# rgb_sensor.net
KiCad netlist of a schematic drawn in EAGLE
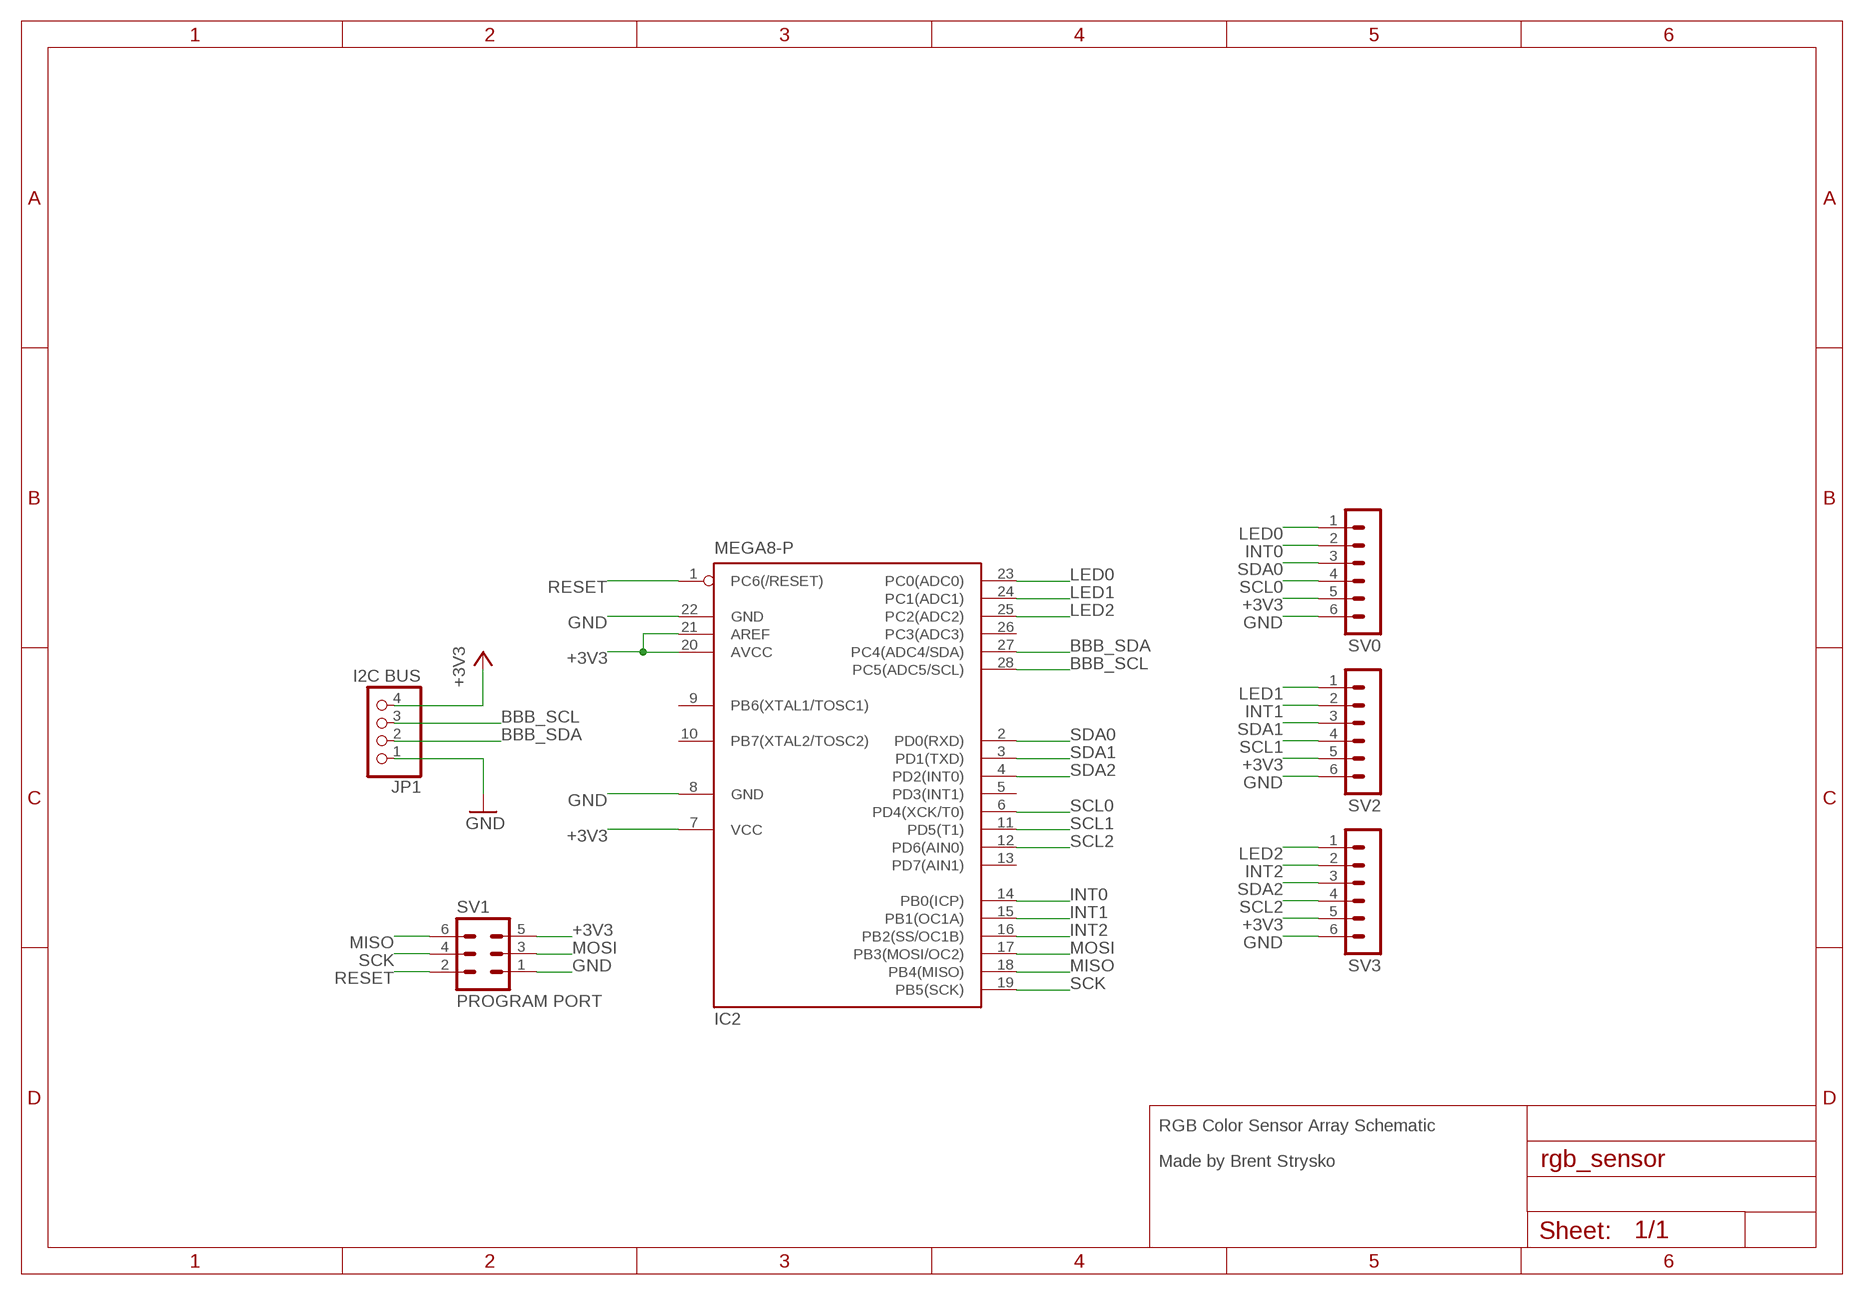
[diagram p0: schematic, sheet 1]

(export (version "E")
  (design (tool "Eeschema 10.0.6"))
  (components
    (comp (ref "IC2")
      (value "MEGA8-P")
      (footprint "eagle-import:DIL28-3")
      (libsource (lib "eagle-import") (part "MEGA8-P"))
    )
    (comp (ref "JP1")
      (value "I2C BUS")
      (footprint "eagle-import:1X04")
      (libsource (lib "eagle-import") (part "PINHD-1X4"))
    )
    (comp (ref "SV0")
      (value "MA06-1")
      (footprint "eagle-import:MA06-1")
      (libsource (lib "eagle-import") (part "MA06-1"))
    )
    (comp (ref "SV1")
      (value "PROGRAM PORT")
      (footprint "eagle-import:MA03-2")
      (libsource (lib "eagle-import") (part "MA03-2"))
    )
    (comp (ref "SV2")
      (value "MA06-1")
      (footprint "eagle-import:MA06-1")
      (libsource (lib "eagle-import") (part "MA06-1"))
    )
    (comp (ref "SV3")
      (value "MA06-1")
      (footprint "eagle-import:MA06-1")
      (libsource (lib "eagle-import") (part "MA06-1"))
    )
  )
  (nets
    (net (code "1") (name "+3V3") (class "Default")
      (node (ref "IC2") (pin "20") (pinfunction "AVCC_20") (pintype "power_in"))
      (node (ref "IC2") (pin "21") (pinfunction "AREF_21") (pintype "passive"))
      (node (ref "IC2") (pin "7") (pinfunction "VCC_7") (pintype "power_in"))
      (node (ref "JP1") (pin "4") (pinfunction "4_4") (pintype "passive"))
      (node (ref "SV0") (pin "5") (pinfunction "5_5") (pintype "passive"))
      (node (ref "SV1") (pin "5") (pinfunction "5_5") (pintype "passive"))
      (node (ref "SV2") (pin "5") (pinfunction "5_5") (pintype "passive"))
      (node (ref "SV3") (pin "5") (pinfunction "5_5") (pintype "passive"))
    )
    (net (code "2") (name "/BBB_SCL") (class "Default")
      (node (ref "IC2") (pin "28") (pinfunction "PC5(ADC5/SCL)_28") (pintype "bidirectional"))
      (node (ref "JP1") (pin "3") (pinfunction "3_3") (pintype "passive"))
    )
    (net (code "3") (name "/BBB_SDA") (class "Default")
      (node (ref "IC2") (pin "27") (pinfunction "PC4(ADC4/SDA)_27") (pintype "bidirectional"))
      (node (ref "JP1") (pin "2") (pinfunction "2_2") (pintype "passive"))
    )
    (net (code "4") (name "/INT0") (class "Default")
      (node (ref "IC2") (pin "14") (pinfunction "PB0(ICP)_14") (pintype "bidirectional"))
      (node (ref "SV0") (pin "2") (pinfunction "2_2") (pintype "passive"))
    )
    (net (code "5") (name "/INT1") (class "Default")
      (node (ref "IC2") (pin "15") (pinfunction "PB1(OC1A)_15") (pintype "bidirectional"))
      (node (ref "SV2") (pin "2") (pinfunction "2_2") (pintype "passive"))
    )
    (net (code "6") (name "/INT2") (class "Default")
      (node (ref "IC2") (pin "16") (pinfunction "PB2(SS/OC1B)_16") (pintype "bidirectional"))
      (node (ref "SV3") (pin "2") (pinfunction "2_2") (pintype "passive"))
    )
    (net (code "7") (name "/LED0") (class "Default")
      (node (ref "IC2") (pin "23") (pinfunction "PC0(ADC0)_23") (pintype "bidirectional"))
      (node (ref "SV0") (pin "1") (pinfunction "1_1") (pintype "passive"))
    )
    (net (code "8") (name "/LED1") (class "Default")
      (node (ref "IC2") (pin "24") (pinfunction "PC1(ADC1)_24") (pintype "bidirectional"))
      (node (ref "SV2") (pin "1") (pinfunction "1_1") (pintype "passive"))
    )
    (net (code "9") (name "/LED2") (class "Default")
      (node (ref "IC2") (pin "25") (pinfunction "PC2(ADC2)_25") (pintype "bidirectional"))
      (node (ref "SV3") (pin "1") (pinfunction "1_1") (pintype "passive"))
    )
    (net (code "10") (name "/MISO") (class "Default")
      (node (ref "IC2") (pin "18") (pinfunction "PB4(MISO)_18") (pintype "bidirectional"))
      (node (ref "SV1") (pin "6") (pinfunction "6_6") (pintype "passive"))
    )
    (net (code "11") (name "/MOSI") (class "Default")
      (node (ref "IC2") (pin "17") (pinfunction "PB3(MOSI/OC2)_17") (pintype "bidirectional"))
      (node (ref "SV1") (pin "3") (pinfunction "3_3") (pintype "passive"))
    )
    (net (code "12") (name "/RESET") (class "Default")
      (node (ref "IC2") (pin "1") (pinfunction "PC6(/RESET)_1") (pintype "bidirectional"))
      (node (ref "SV1") (pin "2") (pinfunction "2_2") (pintype "passive"))
    )
    (net (code "13") (name "/SCK") (class "Default")
      (node (ref "IC2") (pin "19") (pinfunction "PB5(SCK)_19") (pintype "bidirectional"))
      (node (ref "SV1") (pin "4") (pinfunction "4_4") (pintype "passive"))
    )
    (net (code "14") (name "/SCL0") (class "Default")
      (node (ref "IC2") (pin "6") (pinfunction "PD4(XCK/T0)_6") (pintype "bidirectional"))
      (node (ref "SV0") (pin "4") (pinfunction "4_4") (pintype "passive"))
    )
    (net (code "15") (name "/SCL1") (class "Default")
      (node (ref "IC2") (pin "11") (pinfunction "PD5(T1)_11") (pintype "bidirectional"))
      (node (ref "SV2") (pin "4") (pinfunction "4_4") (pintype "passive"))
    )
    (net (code "16") (name "/SCL2") (class "Default")
      (node (ref "IC2") (pin "12") (pinfunction "PD6(AIN0)_12") (pintype "bidirectional"))
      (node (ref "SV3") (pin "4") (pinfunction "4_4") (pintype "passive"))
    )
    (net (code "17") (name "/SDA0") (class "Default")
      (node (ref "IC2") (pin "2") (pinfunction "PD0(RXD)_2") (pintype "bidirectional"))
      (node (ref "SV0") (pin "3") (pinfunction "3_3") (pintype "passive"))
    )
    (net (code "18") (name "/SDA1") (class "Default")
      (node (ref "IC2") (pin "3") (pinfunction "PD1(TXD)_3") (pintype "bidirectional"))
      (node (ref "SV2") (pin "3") (pinfunction "3_3") (pintype "passive"))
    )
    (net (code "19") (name "/SDA2") (class "Default")
      (node (ref "IC2") (pin "4") (pinfunction "PD2(INT0)_4") (pintype "bidirectional"))
      (node (ref "SV3") (pin "3") (pinfunction "3_3") (pintype "passive"))
    )
    (net (code "20") (name "GND") (class "Default")
      (node (ref "IC2") (pin "22") (pinfunction "GND_22") (pintype "power_in"))
      (node (ref "IC2") (pin "8") (pinfunction "GND_8") (pintype "power_in"))
      (node (ref "JP1") (pin "1") (pinfunction "1_1") (pintype "passive"))
      (node (ref "SV0") (pin "6") (pinfunction "6_6") (pintype "passive"))
      (node (ref "SV1") (pin "1") (pinfunction "1_1") (pintype "passive"))
      (node (ref "SV2") (pin "6") (pinfunction "6_6") (pintype "passive"))
      (node (ref "SV3") (pin "6") (pinfunction "6_6") (pintype "passive"))
    )
    (net (code "21") (name "unconnected-(IC2-PB6(XTAL1{slash}TOSC1)-Pad9)") (class "Default")
      (node (ref "IC2") (pin "9") (pinfunction "PB6(XTAL1/TOSC1)_9") (pintype "bidirectional"))
    )
    (net (code "22") (name "unconnected-(IC2-PB7(XTAL2{slash}TOSC2)-Pad10)") (class "Default")
      (node (ref "IC2") (pin "10") (pinfunction "PB7(XTAL2/TOSC2)_10") (pintype "bidirectional"))
    )
    (net (code "23") (name "unconnected-(IC2-PC3(ADC3)-Pad26)") (class "Default")
      (node (ref "IC2") (pin "26") (pinfunction "PC3(ADC3)_26") (pintype "bidirectional"))
    )
    (net (code "24") (name "unconnected-(IC2-PD3(INT1)-Pad5)") (class "Default")
      (node (ref "IC2") (pin "5") (pinfunction "PD3(INT1)_5") (pintype "bidirectional"))
    )
    (net (code "25") (name "unconnected-(IC2-PD7(AIN1)-Pad13)") (class "Default")
      (node (ref "IC2") (pin "13") (pinfunction "PD7(AIN1)_13") (pintype "bidirectional"))
    )
  )
)
